# PowerOut_Top.net
KiCad netlist of a schematic drawn in EAGLE
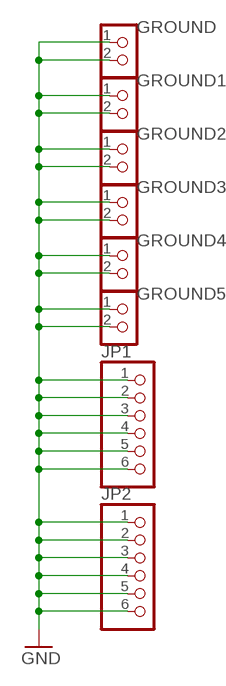
[diagram p0: schematic, sheet 1]

(export (version "E")
  (design (tool "Eeschema 10.0.6"))
  (components
    (comp (ref "GROUND")
      (value "CON_TERMINAL_BLOCK_02-5MM")
      (footprint "eagle-import:TERMINAL_BLOCK_2P_5")
      (libsource (lib "eagle-import") (part "CON_TERMINAL_BLOCK_02-5MM"))
    )
    (comp (ref "GROUND1")
      (value "CON_TERMINAL_BLOCK_02-5MM")
      (footprint "eagle-import:TERMINAL_BLOCK_2P_5")
      (libsource (lib "eagle-import") (part "CON_TERMINAL_BLOCK_02-5MM"))
    )
    (comp (ref "GROUND2")
      (value "CON_TERMINAL_BLOCK_02-5MM")
      (footprint "eagle-import:TERMINAL_BLOCK_2P_5")
      (libsource (lib "eagle-import") (part "CON_TERMINAL_BLOCK_02-5MM"))
    )
    (comp (ref "GROUND3")
      (value "CON_TERMINAL_BLOCK_02-5MM")
      (footprint "eagle-import:TERMINAL_BLOCK_2P_5")
      (libsource (lib "eagle-import") (part "CON_TERMINAL_BLOCK_02-5MM"))
    )
    (comp (ref "GROUND4")
      (value "CON_TERMINAL_BLOCK_02-5MM")
      (footprint "eagle-import:TERMINAL_BLOCK_2P_5")
      (libsource (lib "eagle-import") (part "CON_TERMINAL_BLOCK_02-5MM"))
    )
    (comp (ref "GROUND5")
      (value "CON_TERMINAL_BLOCK_02-5MM")
      (footprint "eagle-import:TERMINAL_BLOCK_2P_5")
      (libsource (lib "eagle-import") (part "CON_TERMINAL_BLOCK_02-5MM"))
    )
    (comp (ref "JP1")
      (value "PINHD-1X6")
      (footprint "eagle-import:1X06")
      (libsource (lib "eagle-import") (part "PINHD-1X6"))
    )
    (comp (ref "JP2")
      (value "PINHD-1X6")
      (footprint "eagle-import:1X06")
      (libsource (lib "eagle-import") (part "PINHD-1X6"))
    )
  )
  (nets
    (net (code "1") (name "GND") (class "Default")
      (node (ref "GROUND") (pin "1") (pinfunction "1_1") (pintype "passive"))
      (node (ref "GROUND") (pin "2") (pinfunction "2_2") (pintype "passive"))
      (node (ref "GROUND1") (pin "1") (pinfunction "1_1") (pintype "passive"))
      (node (ref "GROUND1") (pin "2") (pinfunction "2_2") (pintype "passive"))
      (node (ref "GROUND2") (pin "1") (pinfunction "1_1") (pintype "passive"))
      (node (ref "GROUND2") (pin "2") (pinfunction "2_2") (pintype "passive"))
      (node (ref "GROUND3") (pin "1") (pinfunction "1_1") (pintype "passive"))
      (node (ref "GROUND3") (pin "2") (pinfunction "2_2") (pintype "passive"))
      (node (ref "GROUND4") (pin "1") (pinfunction "1_1") (pintype "passive"))
      (node (ref "GROUND4") (pin "2") (pinfunction "2_2") (pintype "passive"))
      (node (ref "GROUND5") (pin "1") (pinfunction "1_1") (pintype "passive"))
      (node (ref "GROUND5") (pin "2") (pinfunction "2_2") (pintype "passive"))
      (node (ref "JP1") (pin "1") (pinfunction "1_1") (pintype "passive"))
      (node (ref "JP1") (pin "2") (pinfunction "2_2") (pintype "passive"))
      (node (ref "JP1") (pin "3") (pinfunction "3_3") (pintype "passive"))
      (node (ref "JP1") (pin "4") (pinfunction "4_4") (pintype "passive"))
      (node (ref "JP1") (pin "5") (pinfunction "5_5") (pintype "passive"))
      (node (ref "JP1") (pin "6") (pinfunction "6_6") (pintype "passive"))
      (node (ref "JP2") (pin "1") (pinfunction "1_1") (pintype "passive"))
      (node (ref "JP2") (pin "2") (pinfunction "2_2") (pintype "passive"))
      (node (ref "JP2") (pin "3") (pinfunction "3_3") (pintype "passive"))
      (node (ref "JP2") (pin "4") (pinfunction "4_4") (pintype "passive"))
      (node (ref "JP2") (pin "5") (pinfunction "5_5") (pintype "passive"))
      (node (ref "JP2") (pin "6") (pinfunction "6_6") (pintype "passive"))
    )
  )
)
